# LEDFLASHER_RC.net
KiCad netlist of a schematic drawn in Altium Designer
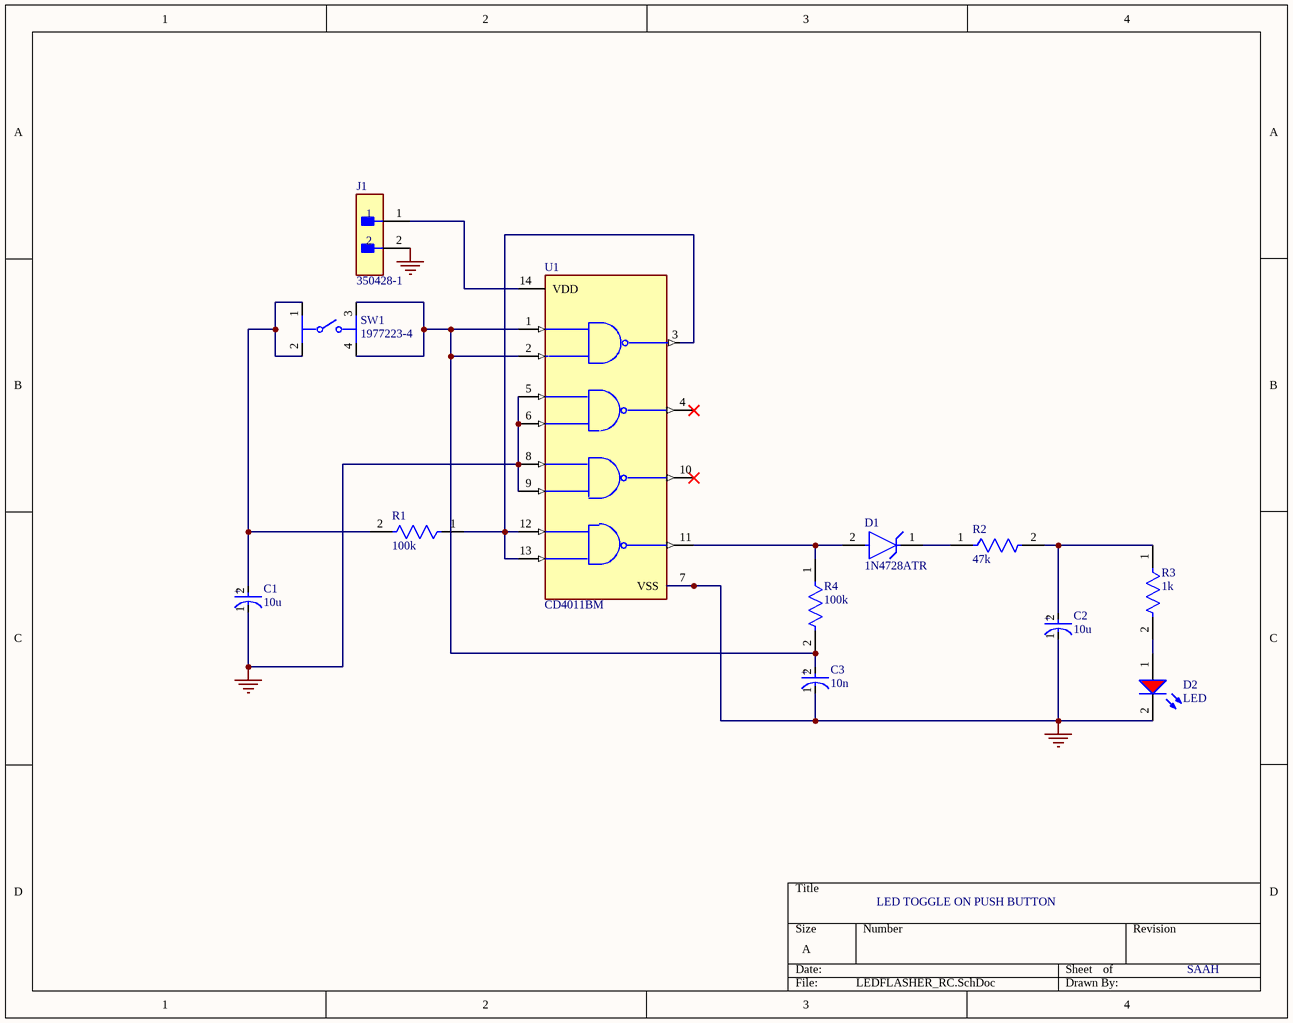
[diagram p0: LEDFLASHER_RC.SchDoc]

(export (version "E")
  (design (tool "Eeschema 10.0.6"))
  (components
    (comp (ref "C1")
      (value "10u")
      (footprint "FP-RAD-TH-D_12_5_0_5-L_20-MFG")
      (description "Aluminum Electrolytic Capacitors (Radial Lead Type) 10uF ±20% 450V")
      (fields (field (name "TOLERANCE") "20%") (field (name "VOLTAGE") "450V"))
      (libsource (lib "Altium Content Vault") (part "a00bbbee19879c290e62620ae7e47b1"))
    )
    (comp (ref "C2")
      (value "10u")
      (footprint "FP-RAD-TH-D_10_0_5-L_20_2-MFG")
      (description "Aluminum Electrolytic Capacitors (Radial Lead Type) 10uF ±20% 400V")
      (fields (field (name "TOLERANCE") "20%") (field (name "VOLTAGE") "400V"))
      (libsource (lib "Altium Content Vault") (part "203bc49f2ac43e59fd269a8c329ed05"))
    )
    (comp (ref "C3")
      (value "10n")
      (footprint "FP-RAD-TH-D_12_5_0_5-L_20-MFG")
      (description "Aluminum Electrolytic Capacitors (Radial Lead Type) 10uF ±20% 450V")
      (fields (field (name "TOLERANCE") "20%") (field (name "VOLTAGE") "450V"))
      (libsource (lib "Altium Content Vault") (part "a00bbbee19879c290e62620ae7e47b1"))
    )
    (comp (ref "D1")
      (value "1N4728ATR")
      (footprint "FP-017AH-MFG")
      (description "1N4728ATR 1N4728 Series 1 W 3.3 V 100 uA Through Hole Zener Diode - DO-41")
      (fields (field (name "TOLERANCE") "5%"))
      (libsource (lib "Altium Content Vault") (part "f813f71cba58e380607f5dd3caf9714"))
    )
    (comp (ref "D2")
      (value "LED")
      (footprint "WL-TMRC_D5.9H8.7")
      (description "151051SS04000 WL-TMRC THT Mono-color Round Color")
      (libsource (lib "Altium Content Vault") (part "LED_Red_1A-2K"))
    )
    (comp (ref "J1")
      (value "350428-1")
      (footprint "FP-350428-1-MFG")
      (description "CONN HEADER VERT 2POS 6.35MM")
      (fields
        (field (name "OCTOPART") "https://octopart.com/350428-1-te+connectivity-46505355")
        (field (name "MANUFACTURER") "TE Connectivity")
      )
      (libsource (lib "Altium Content Vault") (part "3bc925449376181038e59eaffc5286c"))
    )
    (comp (ref "R1")
      (value "100k")
      (footprint "FP-CF14-MFG")
      (description "RES 7.5K OHM 1/4W 5% AXIAL")
      (fields (field (name "TOLERANCE") "5%"))
      (libsource (lib "Altium Content Vault") (part "1029c3af85768c4190bb7ad29bc67b5"))
    )
    (comp (ref "R2")
      (value "47k")
      (footprint "FP-CF14-MFG")
      (description "RES 7.5K OHM 1/4W 5% AXIAL")
      (fields (field (name "TOLERANCE") "5%"))
      (libsource (lib "Altium Content Vault") (part "1029c3af85768c4190bb7ad29bc67b5"))
    )
    (comp (ref "R3")
      (value "1k")
      (footprint "FP-CF14-MFG")
      (description "RES 7.5K OHM 1/4W 5% AXIAL")
      (fields (field (name "TOLERANCE") "5%"))
      (libsource (lib "Altium Content Vault") (part "1029c3af85768c4190bb7ad29bc67b5"))
    )
    (comp (ref "R4")
      (value "100k")
      (footprint "FP-CF14-MFG")
      (description "RES 7.5K OHM 1/4W 5% AXIAL")
      (fields (field (name "TOLERANCE") "5%"))
      (libsource (lib "Altium Content Vault") (part "1029c3af85768c4190bb7ad29bc67b5"))
    )
    (comp (ref "SW1")
      (value "1977223-4")
      (footprint "FP-1977223-4-MFG")
      (description "SWITCH TACTILE SPST-NO 0.05A 12V")
      (libsource (lib "Altium Content Vault") (part "b8895f3f4cefb76e1819d2863dba89b"))
    )
    (comp (ref "U1")
      (value "CD4011BM")
      (footprint "FP-D0014A-MFG")
      (description "IC GATE NAND 4CH 2-INP 14SOIC")
      (fields
        (field (name "OCTOPART") "https://octopart.com/cd4011bm-texas+instruments-16544")
        (field (name "MANUFACTURER") "Texas Instruments")
      )
      (libsource (lib "Altium Content Vault") (part "34aee00f59a36ebc01a0194c7a3f9db"))
    )
  )
  (nets
    (net (code "1") (name "GND") (class "Default")
      (node (ref "C1") (pin "1") (pinfunction "C_1") (pintype "passive"))
      (node (ref "C2") (pin "1") (pinfunction "C_1") (pintype "passive"))
      (node (ref "C3") (pin "1") (pinfunction "C_1") (pintype "passive"))
      (node (ref "D2") (pin "2") (pinfunction "K_2") (pintype "passive"))
      (node (ref "J1") (pin "2") (pinfunction "2_2") (pintype "passive"))
      (node (ref "U1") (pin "5") (pinfunction "C_5") (pintype "input"))
      (node (ref "U1") (pin "6") (pinfunction "D_6") (pintype "input"))
      (node (ref "U1") (pin "7") (pinfunction "VSS_7") (pintype "power_in"))
      (node (ref "U1") (pin "8") (pinfunction "E_8") (pintype "input"))
      (node (ref "U1") (pin "9") (pinfunction "F_9") (pintype "input"))
    )
    (net (code "2") (name "Net-(C1-A)") (class "Default")
      (node (ref "C1") (pin "2") (pinfunction "A_2") (pintype "passive"))
      (node (ref "R1") (pin "2") (pinfunction "2_2") (pintype "passive"))
      (node (ref "SW1") (pin "1") (pinfunction "1_1") (pintype "passive"))
      (node (ref "SW1") (pin "2") (pinfunction "2_2") (pintype "passive"))
    )
    (net (code "3") (name "Net-(C2-A)") (class "Default")
      (node (ref "C2") (pin "2") (pinfunction "A_2") (pintype "passive"))
      (node (ref "R2") (pin "2") (pinfunction "2_2") (pintype "passive"))
      (node (ref "R3") (pin "1") (pinfunction "1_1") (pintype "passive"))
    )
    (net (code "4") (name "Net-(C3-A)") (class "Default")
      (node (ref "C3") (pin "2") (pinfunction "A_2") (pintype "passive"))
      (node (ref "R4") (pin "2") (pinfunction "2_2") (pintype "passive"))
      (node (ref "SW1") (pin "3") (pinfunction "3_3") (pintype "passive"))
      (node (ref "SW1") (pin "4") (pinfunction "4_4") (pintype "passive"))
      (node (ref "U1") (pin "1") (pinfunction "A_1") (pintype "input"))
      (node (ref "U1") (pin "2") (pinfunction "B_2") (pintype "input"))
    )
    (net (code "5") (name "Net-(D1-A)") (class "Default")
      (node (ref "D1") (pin "2") (pinfunction "A_2") (pintype "passive"))
      (node (ref "R4") (pin "1") (pinfunction "1_1") (pintype "passive"))
      (node (ref "U1") (pin "11") (pinfunction "M_11") (pintype "output"))
    )
    (net (code "6") (name "Net-(D1-C)") (class "Default")
      (node (ref "D1") (pin "1") (pinfunction "C_1") (pintype "passive"))
      (node (ref "R2") (pin "1") (pinfunction "1_1") (pintype "passive"))
    )
    (net (code "7") (name "Net-(D2-A)") (class "Default")
      (node (ref "D2") (pin "1") (pinfunction "A_1") (pintype "passive"))
      (node (ref "R3") (pin "2") (pinfunction "2_2") (pintype "passive"))
    )
    (net (code "8") (name "Net-(U1-G)") (class "Default")
      (node (ref "R1") (pin "1") (pinfunction "1_1") (pintype "passive"))
      (node (ref "U1") (pin "12") (pinfunction "G_12") (pintype "input"))
      (node (ref "U1") (pin "13") (pinfunction "H_13") (pintype "input"))
      (node (ref "U1") (pin "3") (pinfunction "J_3") (pintype "output"))
    )
    (net (code "9") (name "Net-(U1-VDD)") (class "Default")
      (node (ref "J1") (pin "1") (pinfunction "1_1") (pintype "passive"))
      (node (ref "U1") (pin "14") (pinfunction "VDD_14") (pintype "power_in"))
    )
    (net (code "10") (name "unconnected-(U1-K-Pad4)") (class "Default")
      (node (ref "U1") (pin "4") (pinfunction "K_4") (pintype "output+no_connect"))
    )
    (net (code "11") (name "unconnected-(U1-L-Pad10)") (class "Default")
      (node (ref "U1") (pin "10") (pinfunction "L_10") (pintype "output+no_connect"))
    )
  )
)
